# buzzer.net
KiCad netlist of a schematic drawn in EAGLE
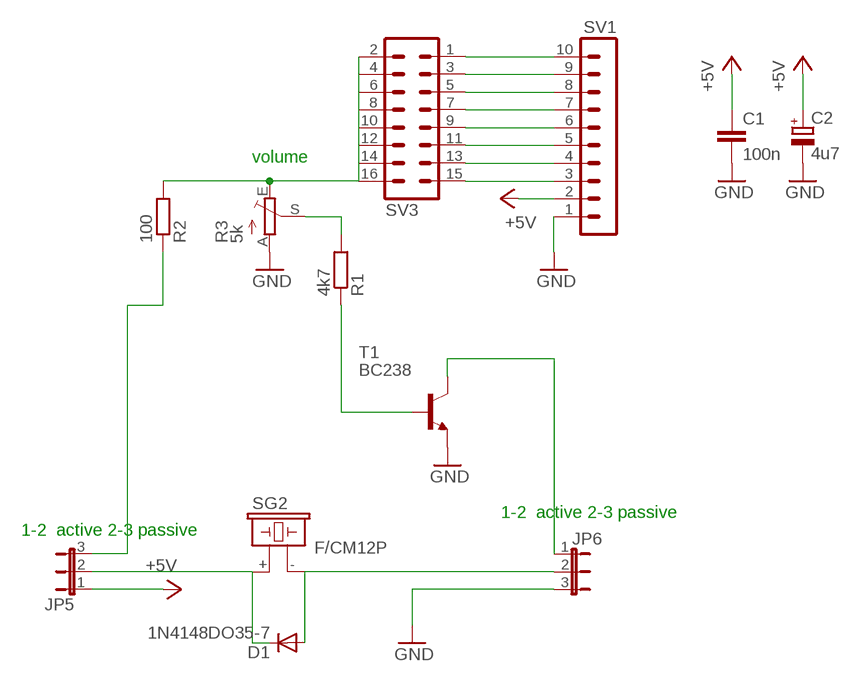
[diagram p0: schematic, sheet 1]

(export (version "E")
  (design (tool "Eeschema 10.0.6"))
  (components
    (comp (ref "C1")
      (value "100n")
      (footprint "eagle-import:C025-024X044")
      (libsource (lib "eagle-import") (part "C-EU025-024X044"))
    )
    (comp (ref "C2")
      (value "4u7")
      (footprint "eagle-import:TT2D5")
      (libsource (lib "eagle-import") (part "CPOL-EUTT2D5"))
    )
    (comp (ref "D1")
      (value "1N4148DO35-7")
      (footprint "eagle-import:DO35-7")
      (libsource (lib "eagle-import") (part "1N4148DO35-7"))
    )
    (comp (ref "JP5")
      (value "JP2W")
      (footprint "eagle-import:JP2W")
      (libsource (lib "eagle-import") (part "JP2W"))
    )
    (comp (ref "JP6")
      (value "JP2W")
      (footprint "eagle-import:JP2W")
      (libsource (lib "eagle-import") (part "JP2W"))
    )
    (comp (ref "R1")
      (value "4k7")
      (footprint "eagle-import:0617_17")
      (libsource (lib "eagle-import") (part "R-EU_0617/17"))
    )
    (comp (ref "R2")
      (value "100")
      (footprint "eagle-import:0207_10")
      (libsource (lib "eagle-import") (part "R-EU_0207/10"))
    )
    (comp (ref "R3")
      (value "5k")
      (footprint "eagle-import:CA9V")
      (libsource (lib "eagle-import") (part "TRIM_EU-CA9V"))
    )
    (comp (ref "SG2")
      (value "F/CM12P")
      (footprint "eagle-import:F_CM12P")
      (libsource (lib "eagle-import") (part "F/CM12P"))
    )
    (comp (ref "SV1")
      (value "MA10-1W")
      (footprint "eagle-import:MA10-1W")
      (libsource (lib "eagle-import") (part "MA10-1W"))
    )
    (comp (ref "SV3")
      (value "MA08-2")
      (footprint "eagle-import:MA08-2")
      (libsource (lib "eagle-import") (part "MA08-2"))
    )
    (comp (ref "T1")
      (value "BC238")
      (footprint "eagle-import:TO5")
      (libsource (lib "eagle-import") (part "-NPN-TO5"))
    )
  )
  (nets
    (net (code "1") (name "+5V") (class "Default")
      (node (ref "C1") (pin "1") (pinfunction "1_1") (pintype "passive"))
      (node (ref "C2") (pin "+") (pinfunction "+_+") (pintype "passive"))
      (node (ref "JP5") (pin "1") (pinfunction "1_1") (pintype "passive"))
      (node (ref "SV1") (pin "2") (pinfunction "2_2") (pintype "passive"))
    )
    (net (code "2") (name "GND") (class "Default")
      (node (ref "C1") (pin "2") (pinfunction "2_2") (pintype "passive"))
      (node (ref "C2") (pin "-") (pinfunction "-_-") (pintype "passive"))
      (node (ref "JP6") (pin "3") (pinfunction "3_3") (pintype "passive"))
      (node (ref "R3") (pin "A") (pinfunction "A_A") (pintype "passive"))
      (node (ref "SV1") (pin "1") (pinfunction "1_1") (pintype "passive"))
      (node (ref "T1") (pin "1") (pinfunction "E_1") (pintype "passive"))
    )
    (net (code "3") (name "Net-(JP5-Pad3)") (class "Default")
      (node (ref "JP5") (pin "3") (pinfunction "3_3") (pintype "passive"))
      (node (ref "R2") (pin "1") (pinfunction "1_1") (pintype "passive"))
    )
    (net (code "4") (name "Net-(R1-Pad2)") (class "Default")
      (node (ref "R1") (pin "2") (pinfunction "2_2") (pintype "passive"))
      (node (ref "R3") (pin "S") (pinfunction "S_S") (pintype "passive"))
    )
    (net (code "5") (name "Net-(R2-Pad2)") (class "Default")
      (node (ref "R2") (pin "2") (pinfunction "2_2") (pintype "passive"))
      (node (ref "R3") (pin "E") (pinfunction "E_E") (pintype "passive"))
      (node (ref "SV3") (pin "10") (pinfunction "10_10") (pintype "passive"))
      (node (ref "SV3") (pin "12") (pinfunction "12_12") (pintype "passive"))
      (node (ref "SV3") (pin "14") (pinfunction "14_14") (pintype "passive"))
      (node (ref "SV3") (pin "16") (pinfunction "16_16") (pintype "passive"))
      (node (ref "SV3") (pin "2") (pinfunction "2_2") (pintype "passive"))
      (node (ref "SV3") (pin "4") (pinfunction "4_4") (pintype "passive"))
      (node (ref "SV3") (pin "6") (pinfunction "6_6") (pintype "passive"))
      (node (ref "SV3") (pin "8") (pinfunction "8_8") (pintype "passive"))
    )
    (net (code "6") (name "Net-(SG2-1)") (class "Default")
      (node (ref "D1") (pin "C") (pinfunction "C_C") (pintype "passive"))
      (node (ref "JP5") (pin "2") (pinfunction "2_2") (pintype "passive"))
      (node (ref "SG2") (pin "+") (pinfunction "1_+") (pintype "passive"))
    )
    (net (code "7") (name "Net-(SG2-2)") (class "Default")
      (node (ref "D1") (pin "A") (pinfunction "A_A") (pintype "passive"))
      (node (ref "JP6") (pin "2") (pinfunction "2_2") (pintype "passive"))
      (node (ref "SG2") (pin "-") (pinfunction "2_-") (pintype "passive"))
    )
    (net (code "8") (name "Net-(SV1-Pad3)") (class "Default")
      (node (ref "SV1") (pin "3") (pinfunction "3_3") (pintype "passive"))
      (node (ref "SV3") (pin "15") (pinfunction "15_15") (pintype "passive"))
    )
    (net (code "9") (name "Net-(SV1-Pad4)") (class "Default")
      (node (ref "SV1") (pin "4") (pinfunction "4_4") (pintype "passive"))
      (node (ref "SV3") (pin "13") (pinfunction "13_13") (pintype "passive"))
    )
    (net (code "10") (name "Net-(SV1-Pad5)") (class "Default")
      (node (ref "SV1") (pin "5") (pinfunction "5_5") (pintype "passive"))
      (node (ref "SV3") (pin "11") (pinfunction "11_11") (pintype "passive"))
    )
    (net (code "11") (name "Net-(SV1-Pad6)") (class "Default")
      (node (ref "SV1") (pin "6") (pinfunction "6_6") (pintype "passive"))
      (node (ref "SV3") (pin "9") (pinfunction "9_9") (pintype "passive"))
    )
    (net (code "12") (name "Net-(SV1-Pad7)") (class "Default")
      (node (ref "SV1") (pin "7") (pinfunction "7_7") (pintype "passive"))
      (node (ref "SV3") (pin "7") (pinfunction "7_7") (pintype "passive"))
    )
    (net (code "13") (name "Net-(SV1-Pad8)") (class "Default")
      (node (ref "SV1") (pin "8") (pinfunction "8_8") (pintype "passive"))
      (node (ref "SV3") (pin "5") (pinfunction "5_5") (pintype "passive"))
    )
    (net (code "14") (name "Net-(SV1-Pad9)") (class "Default")
      (node (ref "SV1") (pin "9") (pinfunction "9_9") (pintype "passive"))
      (node (ref "SV3") (pin "3") (pinfunction "3_3") (pintype "passive"))
    )
    (net (code "15") (name "Net-(SV1-Pad10)") (class "Default")
      (node (ref "SV1") (pin "10") (pinfunction "10_10") (pintype "passive"))
      (node (ref "SV3") (pin "1") (pinfunction "1_1") (pintype "passive"))
    )
    (net (code "16") (name "Net-(T1-B)") (class "Default")
      (node (ref "R1") (pin "1") (pinfunction "1_1") (pintype "passive"))
      (node (ref "T1") (pin "2") (pinfunction "B_2") (pintype "passive"))
    )
    (net (code "17") (name "Net-(T1-C)") (class "Default")
      (node (ref "JP6") (pin "1") (pinfunction "1_1") (pintype "passive"))
      (node (ref "T1") (pin "3") (pinfunction "C_3") (pintype "passive"))
    )
  )
)
